# ssegs_and_registers.net
KiCad netlist of a schematic drawn in Altium Designer
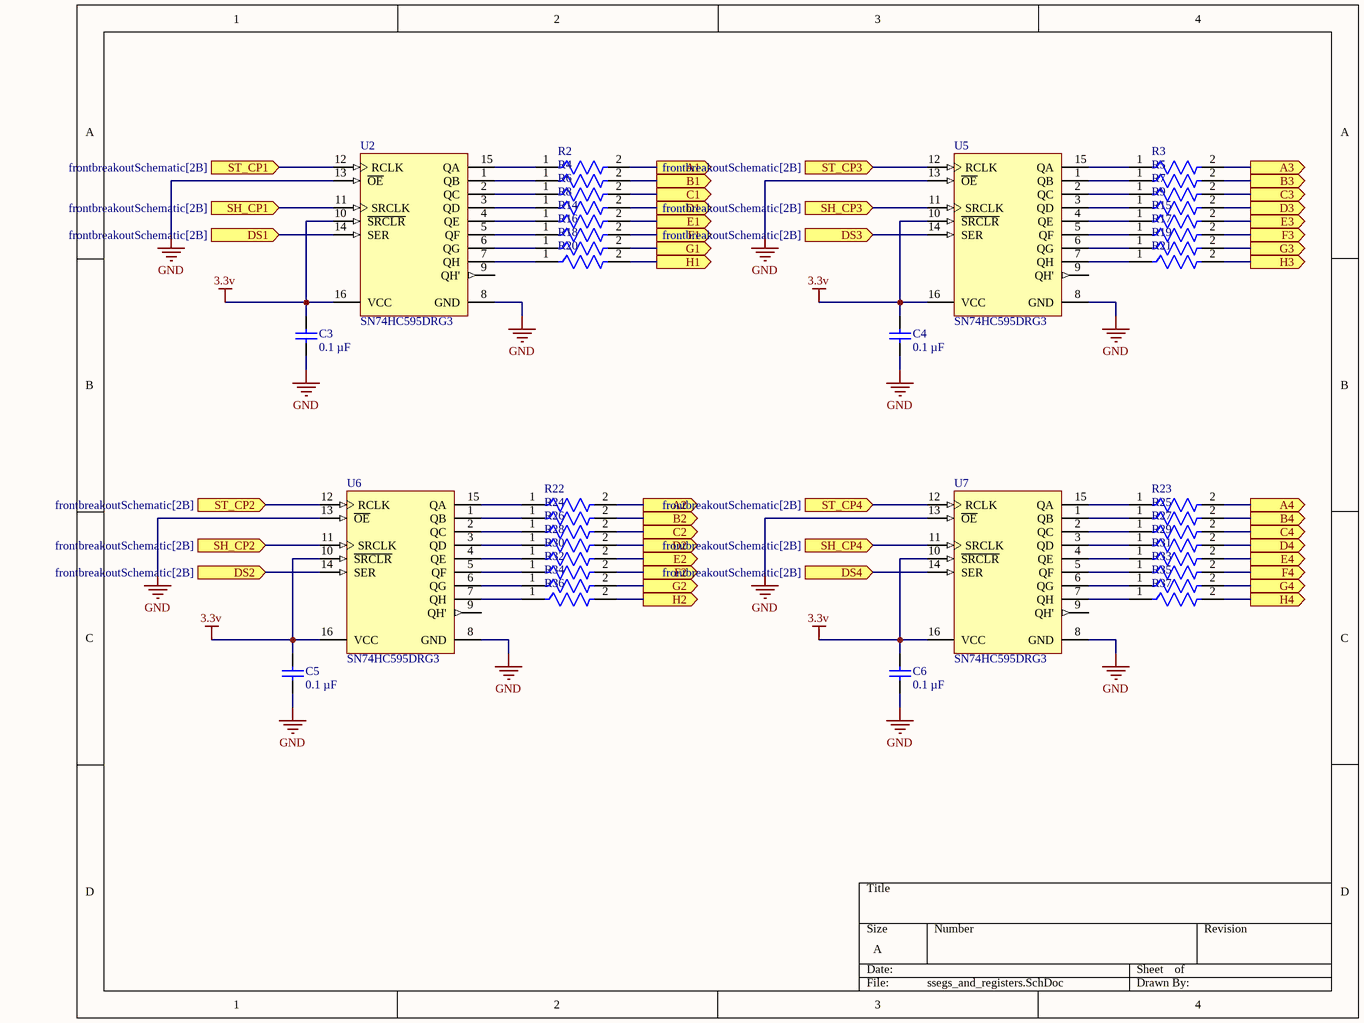
[diagram p0: ssegs_and_registers.SchDoc]

(export (version "E")
  (design (tool "Eeschema 10.0.6"))
  (components
    (comp (ref "C3")
      (value "0.1 µF")
      (footprint "CAPC2013X140X50NL20T25")
      (fields
        (field (name "PART NUMBER") "08055C104K4Z2A")
        (field (name "MANUFACTURER") "AVX Interconnect / Elco")
      )
      (libsource (lib "Altium Content Vault") (part "CAP"))
    )
    (comp (ref "C4")
      (value "0.1 µF")
      (footprint "CAPC2013X140X50NL20T25")
      (fields
        (field (name "PART NUMBER") "08055C104K4Z2A")
        (field (name "MANUFACTURER") "AVX Interconnect / Elco")
      )
      (libsource (lib "Altium Content Vault") (part "CAP"))
    )
    (comp (ref "C5")
      (value "0.1 µF")
      (footprint "CAPC2013X140X50NL20T25")
      (fields
        (field (name "PART NUMBER") "08055C104K4Z2A")
        (field (name "MANUFACTURER") "AVX Interconnect / Elco")
      )
      (libsource (lib "Altium Content Vault") (part "CAP"))
    )
    (comp (ref "C6")
      (value "0.1 µF")
      (footprint "CAPC2013X140X50NL20T25")
      (fields
        (field (name "PART NUMBER") "08055C104K4Z2A")
        (field (name "MANUFACTURER") "AVX Interconnect / Elco")
      )
      (libsource (lib "Altium Content Vault") (part "CAP"))
    )
    (comp (ref "R2")
      (value "200")
      (footprint "FP-RG2012-IPC_A")
      (description "Automotive Metal Thin Film Chip Resistor, 0805, 200Ω, 0.1%, 25ppm/°C, 0.125W, 150VRG2012P-201-B-T5")
      (fields (field (name "TOLERANCE") "0.1%"))
      (libsource (lib "Altium Content Vault") (part "1029c3af85768c4190bb7ad29bc67b5"))
    )
    (comp (ref "R3")
      (value "200")
      (footprint "FP-RG2012-IPC_A")
      (description "Automotive Metal Thin Film Chip Resistor, 0805, 200Ω, 0.1%, 25ppm/°C, 0.125W, 150VRG2012P-201-B-T5")
      (fields (field (name "TOLERANCE") "0.1%"))
      (libsource (lib "Altium Content Vault") (part "1029c3af85768c4190bb7ad29bc67b5"))
    )
    (comp (ref "R4")
      (value "200")
      (footprint "FP-RG2012-IPC_A")
      (description "Automotive Metal Thin Film Chip Resistor, 0805, 200Ω, 0.1%, 25ppm/°C, 0.125W, 150VRG2012P-201-B-T5")
      (fields (field (name "TOLERANCE") "0.1%"))
      (libsource (lib "Altium Content Vault") (part "1029c3af85768c4190bb7ad29bc67b5"))
    )
    (comp (ref "R5")
      (value "200")
      (footprint "FP-RG2012-IPC_A")
      (description "Automotive Metal Thin Film Chip Resistor, 0805, 200Ω, 0.1%, 25ppm/°C, 0.125W, 150VRG2012P-201-B-T5")
      (fields (field (name "TOLERANCE") "0.1%"))
      (libsource (lib "Altium Content Vault") (part "1029c3af85768c4190bb7ad29bc67b5"))
    )
    (comp (ref "R6")
      (value "200")
      (footprint "FP-RG2012-IPC_A")
      (description "Automotive Metal Thin Film Chip Resistor, 0805, 200Ω, 0.1%, 25ppm/°C, 0.125W, 150VRG2012P-201-B-T5")
      (fields (field (name "TOLERANCE") "0.1%"))
      (libsource (lib "Altium Content Vault") (part "1029c3af85768c4190bb7ad29bc67b5"))
    )
    (comp (ref "R7")
      (value "200")
      (footprint "FP-RG2012-IPC_A")
      (description "Automotive Metal Thin Film Chip Resistor, 0805, 200Ω, 0.1%, 25ppm/°C, 0.125W, 150VRG2012P-201-B-T5")
      (fields (field (name "TOLERANCE") "0.1%"))
      (libsource (lib "Altium Content Vault") (part "1029c3af85768c4190bb7ad29bc67b5"))
    )
    (comp (ref "R8")
      (value "200")
      (footprint "FP-RG2012-IPC_A")
      (description "Automotive Metal Thin Film Chip Resistor, 0805, 200Ω, 0.1%, 25ppm/°C, 0.125W, 150VRG2012P-201-B-T5")
      (fields (field (name "TOLERANCE") "0.1%"))
      (libsource (lib "Altium Content Vault") (part "1029c3af85768c4190bb7ad29bc67b5"))
    )
    (comp (ref "R9")
      (value "200")
      (footprint "FP-RG2012-IPC_A")
      (description "Automotive Metal Thin Film Chip Resistor, 0805, 200Ω, 0.1%, 25ppm/°C, 0.125W, 150VRG2012P-201-B-T5")
      (fields (field (name "TOLERANCE") "0.1%"))
      (libsource (lib "Altium Content Vault") (part "1029c3af85768c4190bb7ad29bc67b5"))
    )
    (comp (ref "R14")
      (value "200")
      (footprint "FP-RG2012-IPC_A")
      (description "Automotive Metal Thin Film Chip Resistor, 0805, 200Ω, 0.1%, 25ppm/°C, 0.125W, 150VRG2012P-201-B-T5")
      (fields (field (name "TOLERANCE") "0.1%"))
      (libsource (lib "Altium Content Vault") (part "1029c3af85768c4190bb7ad29bc67b5"))
    )
    (comp (ref "R15")
      (value "200")
      (footprint "FP-RG2012-IPC_A")
      (description "Automotive Metal Thin Film Chip Resistor, 0805, 200Ω, 0.1%, 25ppm/°C, 0.125W, 150VRG2012P-201-B-T5")
      (fields (field (name "TOLERANCE") "0.1%"))
      (libsource (lib "Altium Content Vault") (part "1029c3af85768c4190bb7ad29bc67b5"))
    )
    (comp (ref "R16")
      (value "200")
      (footprint "FP-RG2012-IPC_A")
      (description "Automotive Metal Thin Film Chip Resistor, 0805, 200Ω, 0.1%, 25ppm/°C, 0.125W, 150VRG2012P-201-B-T5")
      (fields (field (name "TOLERANCE") "0.1%"))
      (libsource (lib "Altium Content Vault") (part "1029c3af85768c4190bb7ad29bc67b5"))
    )
    (comp (ref "R17")
      (value "200")
      (footprint "FP-RG2012-IPC_A")
      (description "Automotive Metal Thin Film Chip Resistor, 0805, 200Ω, 0.1%, 25ppm/°C, 0.125W, 150VRG2012P-201-B-T5")
      (fields (field (name "TOLERANCE") "0.1%"))
      (libsource (lib "Altium Content Vault") (part "1029c3af85768c4190bb7ad29bc67b5"))
    )
    (comp (ref "R18")
      (value "200")
      (footprint "FP-RG2012-IPC_A")
      (description "Automotive Metal Thin Film Chip Resistor, 0805, 200Ω, 0.1%, 25ppm/°C, 0.125W, 150VRG2012P-201-B-T5")
      (fields (field (name "TOLERANCE") "0.1%"))
      (libsource (lib "Altium Content Vault") (part "1029c3af85768c4190bb7ad29bc67b5"))
    )
    (comp (ref "R19")
      (value "200")
      (footprint "FP-RG2012-IPC_A")
      (description "Automotive Metal Thin Film Chip Resistor, 0805, 200Ω, 0.1%, 25ppm/°C, 0.125W, 150VRG2012P-201-B-T5")
      (fields (field (name "TOLERANCE") "0.1%"))
      (libsource (lib "Altium Content Vault") (part "1029c3af85768c4190bb7ad29bc67b5"))
    )
    (comp (ref "R20")
      (value "200")
      (footprint "FP-RG2012-IPC_A")
      (description "Automotive Metal Thin Film Chip Resistor, 0805, 200Ω, 0.1%, 25ppm/°C, 0.125W, 150VRG2012P-201-B-T5")
      (fields (field (name "TOLERANCE") "0.1%"))
      (libsource (lib "Altium Content Vault") (part "1029c3af85768c4190bb7ad29bc67b5"))
    )
    (comp (ref "R21")
      (value "200")
      (footprint "FP-RG2012-IPC_A")
      (description "Automotive Metal Thin Film Chip Resistor, 0805, 200Ω, 0.1%, 25ppm/°C, 0.125W, 150VRG2012P-201-B-T5")
      (fields (field (name "TOLERANCE") "0.1%"))
      (libsource (lib "Altium Content Vault") (part "1029c3af85768c4190bb7ad29bc67b5"))
    )
    (comp (ref "R22")
      (value "200")
      (footprint "FP-RG2012-IPC_A")
      (description "Automotive Metal Thin Film Chip Resistor, 0805, 200Ω, 0.1%, 25ppm/°C, 0.125W, 150VRG2012P-201-B-T5")
      (fields (field (name "TOLERANCE") "0.1%"))
      (libsource (lib "Altium Content Vault") (part "1029c3af85768c4190bb7ad29bc67b5"))
    )
    (comp (ref "R23")
      (value "200")
      (footprint "FP-RG2012-IPC_A")
      (description "Automotive Metal Thin Film Chip Resistor, 0805, 200Ω, 0.1%, 25ppm/°C, 0.125W, 150VRG2012P-201-B-T5")
      (fields (field (name "TOLERANCE") "0.1%"))
      (libsource (lib "Altium Content Vault") (part "1029c3af85768c4190bb7ad29bc67b5"))
    )
    (comp (ref "R24")
      (value "200")
      (footprint "FP-RG2012-IPC_A")
      (description "Automotive Metal Thin Film Chip Resistor, 0805, 200Ω, 0.1%, 25ppm/°C, 0.125W, 150VRG2012P-201-B-T5")
      (fields (field (name "TOLERANCE") "0.1%"))
      (libsource (lib "Altium Content Vault") (part "1029c3af85768c4190bb7ad29bc67b5"))
    )
    (comp (ref "R25")
      (value "200")
      (footprint "FP-RG2012-IPC_A")
      (description "Automotive Metal Thin Film Chip Resistor, 0805, 200Ω, 0.1%, 25ppm/°C, 0.125W, 150VRG2012P-201-B-T5")
      (fields (field (name "TOLERANCE") "0.1%"))
      (libsource (lib "Altium Content Vault") (part "1029c3af85768c4190bb7ad29bc67b5"))
    )
    (comp (ref "R26")
      (value "200")
      (footprint "FP-RG2012-IPC_A")
      (description "Automotive Metal Thin Film Chip Resistor, 0805, 200Ω, 0.1%, 25ppm/°C, 0.125W, 150VRG2012P-201-B-T5")
      (fields (field (name "TOLERANCE") "0.1%"))
      (libsource (lib "Altium Content Vault") (part "1029c3af85768c4190bb7ad29bc67b5"))
    )
    (comp (ref "R27")
      (value "200")
      (footprint "FP-RG2012-IPC_A")
      (description "Automotive Metal Thin Film Chip Resistor, 0805, 200Ω, 0.1%, 25ppm/°C, 0.125W, 150VRG2012P-201-B-T5")
      (fields (field (name "TOLERANCE") "0.1%"))
      (libsource (lib "Altium Content Vault") (part "1029c3af85768c4190bb7ad29bc67b5"))
    )
    (comp (ref "R28")
      (value "200")
      (footprint "FP-RG2012-IPC_A")
      (description "Automotive Metal Thin Film Chip Resistor, 0805, 200Ω, 0.1%, 25ppm/°C, 0.125W, 150VRG2012P-201-B-T5")
      (fields (field (name "TOLERANCE") "0.1%"))
      (libsource (lib "Altium Content Vault") (part "1029c3af85768c4190bb7ad29bc67b5"))
    )
    (comp (ref "R29")
      (value "200")
      (footprint "FP-RG2012-IPC_A")
      (description "Automotive Metal Thin Film Chip Resistor, 0805, 200Ω, 0.1%, 25ppm/°C, 0.125W, 150VRG2012P-201-B-T5")
      (fields (field (name "TOLERANCE") "0.1%"))
      (libsource (lib "Altium Content Vault") (part "1029c3af85768c4190bb7ad29bc67b5"))
    )
    (comp (ref "R30")
      (value "200")
      (footprint "FP-RG2012-IPC_A")
      (description "Automotive Metal Thin Film Chip Resistor, 0805, 200Ω, 0.1%, 25ppm/°C, 0.125W, 150VRG2012P-201-B-T5")
      (fields (field (name "TOLERANCE") "0.1%"))
      (libsource (lib "Altium Content Vault") (part "1029c3af85768c4190bb7ad29bc67b5"))
    )
    (comp (ref "R31")
      (value "200")
      (footprint "FP-RG2012-IPC_A")
      (description "Automotive Metal Thin Film Chip Resistor, 0805, 200Ω, 0.1%, 25ppm/°C, 0.125W, 150VRG2012P-201-B-T5")
      (fields (field (name "TOLERANCE") "0.1%"))
      (libsource (lib "Altium Content Vault") (part "1029c3af85768c4190bb7ad29bc67b5"))
    )
    (comp (ref "R32")
      (value "200")
      (footprint "FP-RG2012-IPC_A")
      (description "Automotive Metal Thin Film Chip Resistor, 0805, 200Ω, 0.1%, 25ppm/°C, 0.125W, 150VRG2012P-201-B-T5")
      (fields (field (name "TOLERANCE") "0.1%"))
      (libsource (lib "Altium Content Vault") (part "1029c3af85768c4190bb7ad29bc67b5"))
    )
    (comp (ref "R33")
      (value "200")
      (footprint "FP-RG2012-IPC_A")
      (description "Automotive Metal Thin Film Chip Resistor, 0805, 200Ω, 0.1%, 25ppm/°C, 0.125W, 150VRG2012P-201-B-T5")
      (fields (field (name "TOLERANCE") "0.1%"))
      (libsource (lib "Altium Content Vault") (part "1029c3af85768c4190bb7ad29bc67b5"))
    )
    (comp (ref "R34")
      (value "200")
      (footprint "FP-RG2012-IPC_A")
      (description "Automotive Metal Thin Film Chip Resistor, 0805, 200Ω, 0.1%, 25ppm/°C, 0.125W, 150VRG2012P-201-B-T5")
      (fields (field (name "TOLERANCE") "0.1%"))
      (libsource (lib "Altium Content Vault") (part "1029c3af85768c4190bb7ad29bc67b5"))
    )
    (comp (ref "R35")
      (value "200")
      (footprint "FP-RG2012-IPC_A")
      (description "Automotive Metal Thin Film Chip Resistor, 0805, 200Ω, 0.1%, 25ppm/°C, 0.125W, 150VRG2012P-201-B-T5")
      (fields (field (name "TOLERANCE") "0.1%"))
      (libsource (lib "Altium Content Vault") (part "1029c3af85768c4190bb7ad29bc67b5"))
    )
    (comp (ref "R36")
      (value "200")
      (footprint "FP-RG2012-IPC_A")
      (description "Automotive Metal Thin Film Chip Resistor, 0805, 200Ω, 0.1%, 25ppm/°C, 0.125W, 150VRG2012P-201-B-T5")
      (fields (field (name "TOLERANCE") "0.1%"))
      (libsource (lib "Altium Content Vault") (part "1029c3af85768c4190bb7ad29bc67b5"))
    )
    (comp (ref "R37")
      (value "200")
      (footprint "FP-RG2012-IPC_A")
      (description "Automotive Metal Thin Film Chip Resistor, 0805, 200Ω, 0.1%, 25ppm/°C, 0.125W, 150VRG2012P-201-B-T5")
      (fields (field (name "TOLERANCE") "0.1%"))
      (libsource (lib "Altium Content Vault") (part "1029c3af85768c4190bb7ad29bc67b5"))
    )
    (comp (ref "U2")
      (value "SN74HC595DRG3")
      (footprint "D0016A_L")
      (description "8-Bit Shift Registers With 3-State Output Registers, D0016A, LARGE T&R")
      (fields
        (field (name "MANUFACTURER") "Texas Instruments")
        (field (name "GENERIC PART NUMBER") "SN74HC595")
      )
      (libsource (lib "Altium Content Vault") (part "TI-SN74XHCT595X_SN74LV595A-16"))
    )
    (comp (ref "U5")
      (value "SN74HC595DRG3")
      (footprint "D0016A_L")
      (description "8-Bit Shift Registers With 3-State Output Registers, D0016A, LARGE T&R")
      (fields
        (field (name "MANUFACTURER") "Texas Instruments")
        (field (name "GENERIC PART NUMBER") "SN74HC595")
      )
      (libsource (lib "Altium Content Vault") (part "TI-SN74XHCT595X_SN74LV595A-16"))
    )
    (comp (ref "U6")
      (value "SN74HC595DRG3")
      (footprint "D0016A_L")
      (description "8-Bit Shift Registers With 3-State Output Registers, D0016A, LARGE T&R")
      (fields
        (field (name "MANUFACTURER") "Texas Instruments")
        (field (name "GENERIC PART NUMBER") "SN74HC595")
      )
      (libsource (lib "Altium Content Vault") (part "TI-SN74XHCT595X_SN74LV595A-16"))
    )
    (comp (ref "U7")
      (value "SN74HC595DRG3")
      (footprint "D0016A_L")
      (description "8-Bit Shift Registers With 3-State Output Registers, D0016A, LARGE T&R")
      (fields
        (field (name "MANUFACTURER") "Texas Instruments")
        (field (name "GENERIC PART NUMBER") "SN74HC595")
      )
      (libsource (lib "Altium Content Vault") (part "TI-SN74XHCT595X_SN74LV595A-16"))
    )
  )
  (nets
    (net (code "1") (name "/A1") (class "Default")
      (node (ref "R2") (pin "2") (pinfunction "2_2") (pintype "passive"))
    )
    (net (code "2") (name "/A2") (class "Default")
      (node (ref "R22") (pin "2") (pinfunction "2_2") (pintype "passive"))
    )
    (net (code "3") (name "/A3") (class "Default")
      (node (ref "R3") (pin "2") (pinfunction "2_2") (pintype "passive"))
    )
    (net (code "4") (name "/A4") (class "Default")
      (node (ref "R23") (pin "2") (pinfunction "2_2") (pintype "passive"))
    )
    (net (code "5") (name "/B1") (class "Default")
      (node (ref "R4") (pin "2") (pinfunction "2_2") (pintype "passive"))
    )
    (net (code "6") (name "/B2") (class "Default")
      (node (ref "R24") (pin "2") (pinfunction "2_2") (pintype "passive"))
    )
    (net (code "7") (name "/B3") (class "Default")
      (node (ref "R5") (pin "2") (pinfunction "2_2") (pintype "passive"))
    )
    (net (code "8") (name "/B4") (class "Default")
      (node (ref "R25") (pin "2") (pinfunction "2_2") (pintype "passive"))
    )
    (net (code "9") (name "/C1") (class "Default")
      (node (ref "R6") (pin "2") (pinfunction "2_2") (pintype "passive"))
    )
    (net (code "10") (name "/C2") (class "Default")
      (node (ref "R26") (pin "2") (pinfunction "2_2") (pintype "passive"))
    )
    (net (code "11") (name "/C3") (class "Default")
      (node (ref "R7") (pin "2") (pinfunction "2_2") (pintype "passive"))
    )
    (net (code "12") (name "/C4") (class "Default")
      (node (ref "R27") (pin "2") (pinfunction "2_2") (pintype "passive"))
    )
    (net (code "13") (name "/D1") (class "Default")
      (node (ref "R8") (pin "2") (pinfunction "2_2") (pintype "passive"))
    )
    (net (code "14") (name "/D2") (class "Default")
      (node (ref "R28") (pin "2") (pinfunction "2_2") (pintype "passive"))
    )
    (net (code "15") (name "/D3") (class "Default")
      (node (ref "R9") (pin "2") (pinfunction "2_2") (pintype "passive"))
    )
    (net (code "16") (name "/D4") (class "Default")
      (node (ref "R29") (pin "2") (pinfunction "2_2") (pintype "passive"))
    )
    (net (code "17") (name "/DS1") (class "Default")
      (node (ref "U2") (pin "14") (pinfunction "SER_14") (pintype "input"))
    )
    (net (code "18") (name "/DS2") (class "Default")
      (node (ref "U6") (pin "14") (pinfunction "SER_14") (pintype "input"))
    )
    (net (code "19") (name "/DS3") (class "Default")
      (node (ref "U5") (pin "14") (pinfunction "SER_14") (pintype "input"))
    )
    (net (code "20") (name "/DS4") (class "Default")
      (node (ref "U7") (pin "14") (pinfunction "SER_14") (pintype "input"))
    )
    (net (code "21") (name "/E1") (class "Default")
      (node (ref "R14") (pin "2") (pinfunction "2_2") (pintype "passive"))
    )
    (net (code "22") (name "/E2") (class "Default")
      (node (ref "R30") (pin "2") (pinfunction "2_2") (pintype "passive"))
    )
    (net (code "23") (name "/E3") (class "Default")
      (node (ref "R15") (pin "2") (pinfunction "2_2") (pintype "passive"))
    )
    (net (code "24") (name "/E4") (class "Default")
      (node (ref "R31") (pin "2") (pinfunction "2_2") (pintype "passive"))
    )
    (net (code "25") (name "/F1") (class "Default")
      (node (ref "R16") (pin "2") (pinfunction "2_2") (pintype "passive"))
    )
    (net (code "26") (name "/F2") (class "Default")
      (node (ref "R32") (pin "2") (pinfunction "2_2") (pintype "passive"))
    )
    (net (code "27") (name "/F3") (class "Default")
      (node (ref "R17") (pin "2") (pinfunction "2_2") (pintype "passive"))
    )
    (net (code "28") (name "/F4") (class "Default")
      (node (ref "R33") (pin "2") (pinfunction "2_2") (pintype "passive"))
    )
    (net (code "29") (name "/G1") (class "Default")
      (node (ref "R18") (pin "2") (pinfunction "2_2") (pintype "passive"))
    )
    (net (code "30") (name "/G2") (class "Default")
      (node (ref "R34") (pin "2") (pinfunction "2_2") (pintype "passive"))
    )
    (net (code "31") (name "/G3") (class "Default")
      (node (ref "R19") (pin "2") (pinfunction "2_2") (pintype "passive"))
    )
    (net (code "32") (name "/G4") (class "Default")
      (node (ref "R35") (pin "2") (pinfunction "2_2") (pintype "passive"))
    )
    (net (code "33") (name "/H1") (class "Default")
      (node (ref "R20") (pin "2") (pinfunction "2_2") (pintype "passive"))
    )
    (net (code "34") (name "/H2") (class "Default")
      (node (ref "R36") (pin "2") (pinfunction "2_2") (pintype "passive"))
    )
    (net (code "35") (name "/H3") (class "Default")
      (node (ref "R21") (pin "2") (pinfunction "2_2") (pintype "passive"))
    )
    (net (code "36") (name "/H4") (class "Default")
      (node (ref "R37") (pin "2") (pinfunction "2_2") (pintype "passive"))
    )
    (net (code "37") (name "/SH_CP1") (class "Default")
      (node (ref "U2") (pin "11") (pinfunction "SRCLK_11") (pintype "input"))
    )
    (net (code "38") (name "/SH_CP2") (class "Default")
      (node (ref "U6") (pin "11") (pinfunction "SRCLK_11") (pintype "input"))
    )
    (net (code "39") (name "/SH_CP3") (class "Default")
      (node (ref "U5") (pin "11") (pinfunction "SRCLK_11") (pintype "input"))
    )
    (net (code "40") (name "/SH_CP4") (class "Default")
      (node (ref "U7") (pin "11") (pinfunction "SRCLK_11") (pintype "input"))
    )
    (net (code "41") (name "/ST_CP1") (class "Default")
      (node (ref "U2") (pin "12") (pinfunction "RCLK_12") (pintype "input"))
    )
    (net (code "42") (name "/ST_CP2") (class "Default")
      (node (ref "U6") (pin "12") (pinfunction "RCLK_12") (pintype "input"))
    )
    (net (code "43") (name "/ST_CP3") (class "Default")
      (node (ref "U5") (pin "12") (pinfunction "RCLK_12") (pintype "input"))
    )
    (net (code "44") (name "/ST_CP4") (class "Default")
      (node (ref "U7") (pin "12") (pinfunction "RCLK_12") (pintype "input"))
    )
    (net (code "45") (name "3.3v") (class "Default")
      (node (ref "C3") (pin "1") (pinfunction "1_1") (pintype "passive"))
      (node (ref "C4") (pin "1") (pinfunction "1_1") (pintype "passive"))
      (node (ref "C5") (pin "1") (pinfunction "1_1") (pintype "passive"))
      (node (ref "C6") (pin "1") (pinfunction "1_1") (pintype "passive"))
      (node (ref "U2") (pin "10") (pinfunction "~{SRCLR}_10") (pintype "input"))
      (node (ref "U2") (pin "16") (pinfunction "VCC_16") (pintype "power_in"))
      (node (ref "U5") (pin "10") (pinfunction "~{SRCLR}_10") (pintype "input"))
      (node (ref "U5") (pin "16") (pinfunction "VCC_16") (pintype "power_in"))
      (node (ref "U6") (pin "10") (pinfunction "~{SRCLR}_10") (pintype "input"))
      (node (ref "U6") (pin "16") (pinfunction "VCC_16") (pintype "power_in"))
      (node (ref "U7") (pin "10") (pinfunction "~{SRCLR}_10") (pintype "input"))
      (node (ref "U7") (pin "16") (pinfunction "VCC_16") (pintype "power_in"))
    )
    (net (code "46") (name "GND") (class "Default")
      (node (ref "C3") (pin "2") (pinfunction "2_2") (pintype "passive"))
      (node (ref "C4") (pin "2") (pinfunction "2_2") (pintype "passive"))
      (node (ref "C5") (pin "2") (pinfunction "2_2") (pintype "passive"))
      (node (ref "C6") (pin "2") (pinfunction "2_2") (pintype "passive"))
      (node (ref "U2") (pin "13") (pinfunction "~{OE}_13") (pintype "input"))
      (node (ref "U2") (pin "8") (pinfunction "GND_8") (pintype "power_in"))
      (node (ref "U5") (pin "13") (pinfunction "~{OE}_13") (pintype "input"))
      (node (ref "U5") (pin "8") (pinfunction "GND_8") (pintype "power_in"))
      (node (ref "U6") (pin "13") (pinfunction "~{OE}_13") (pintype "input"))
      (node (ref "U6") (pin "8") (pinfunction "GND_8") (pintype "power_in"))
      (node (ref "U7") (pin "13") (pinfunction "~{OE}_13") (pintype "input"))
      (node (ref "U7") (pin "8") (pinfunction "GND_8") (pintype "power_in"))
    )
    (net (code "47") (name "Net-(U2-QA)") (class "Default")
      (node (ref "R2") (pin "1") (pinfunction "1_1") (pintype "passive"))
      (node (ref "U2") (pin "15") (pinfunction "QA_15") (pintype "tri_state"))
    )
    (net (code "48") (name "Net-(U2-QB)") (class "Default")
      (node (ref "R4") (pin "1") (pinfunction "1_1") (pintype "passive"))
      (node (ref "U2") (pin "1") (pinfunction "QB_1") (pintype "tri_state"))
    )
    (net (code "49") (name "Net-(U2-QC)") (class "Default")
      (node (ref "R6") (pin "1") (pinfunction "1_1") (pintype "passive"))
      (node (ref "U2") (pin "2") (pinfunction "QC_2") (pintype "tri_state"))
    )
    (net (code "50") (name "Net-(U2-QD)") (class "Default")
      (node (ref "R8") (pin "1") (pinfunction "1_1") (pintype "passive"))
      (node (ref "U2") (pin "3") (pinfunction "QD_3") (pintype "tri_state"))
    )
    (net (code "51") (name "Net-(U2-QE)") (class "Default")
      (node (ref "R14") (pin "1") (pinfunction "1_1") (pintype "passive"))
      (node (ref "U2") (pin "4") (pinfunction "QE_4") (pintype "tri_state"))
    )
    (net (code "52") (name "Net-(U2-QF)") (class "Default")
      (node (ref "R16") (pin "1") (pinfunction "1_1") (pintype "passive"))
      (node (ref "U2") (pin "5") (pinfunction "QF_5") (pintype "tri_state"))
    )
    (net (code "53") (name "Net-(U2-QG)") (class "Default")
      (node (ref "R18") (pin "1") (pinfunction "1_1") (pintype "passive"))
      (node (ref "U2") (pin "6") (pinfunction "QG_6") (pintype "tri_state"))
    )
    (net (code "54") (name "Net-(U2-QH)") (class "Default")
      (node (ref "R20") (pin "1") (pinfunction "1_1") (pintype "passive"))
      (node (ref "U2") (pin "7") (pinfunction "QH_7") (pintype "tri_state"))
    )
    (net (code "55") (name "Net-(U5-QA)") (class "Default")
      (node (ref "R3") (pin "1") (pinfunction "1_1") (pintype "passive"))
      (node (ref "U5") (pin "15") (pinfunction "QA_15") (pintype "tri_state"))
    )
    (net (code "56") (name "Net-(U5-QB)") (class "Default")
      (node (ref "R5") (pin "1") (pinfunction "1_1") (pintype "passive"))
      (node (ref "U5") (pin "1") (pinfunction "QB_1") (pintype "tri_state"))
    )
    (net (code "57") (name "Net-(U5-QC)") (class "Default")
      (node (ref "R7") (pin "1") (pinfunction "1_1") (pintype "passive"))
      (node (ref "U5") (pin "2") (pinfunction "QC_2") (pintype "tri_state"))
    )
    (net (code "58") (name "Net-(U5-QD)") (class "Default")
      (node (ref "R9") (pin "1") (pinfunction "1_1") (pintype "passive"))
      (node (ref "U5") (pin "3") (pinfunction "QD_3") (pintype "tri_state"))
    )
    (net (code "59") (name "Net-(U5-QE)") (class "Default")
      (node (ref "R15") (pin "1") (pinfunction "1_1") (pintype "passive"))
      (node (ref "U5") (pin "4") (pinfunction "QE_4") (pintype "tri_state"))
    )
    (net (code "60") (name "Net-(U5-QF)") (class "Default")
      (node (ref "R17") (pin "1") (pinfunction "1_1") (pintype "passive"))
      (node (ref "U5") (pin "5") (pinfunction "QF_5") (pintype "tri_state"))
    )
    (net (code "61") (name "Net-(U5-QG)") (class "Default")
      (node (ref "R19") (pin "1") (pinfunction "1_1") (pintype "passive"))
      (node (ref "U5") (pin "6") (pinfunction "QG_6") (pintype "tri_state"))
    )
    (net (code "62") (name "Net-(U5-QH)") (class "Default")
      (node (ref "R21") (pin "1") (pinfunction "1_1") (pintype "passive"))
      (node (ref "U5") (pin "7") (pinfunction "QH_7") (pintype "tri_state"))
    )
    (net (code "63") (name "Net-(U6-QA)") (class "Default")
      (node (ref "R22") (pin "1") (pinfunction "1_1") (pintype "passive"))
      (node (ref "U6") (pin "15") (pinfunction "QA_15") (pintype "tri_state"))
    )
    (net (code "64") (name "Net-(U6-QB)") (class "Default")
      (node (ref "R24") (pin "1") (pinfunction "1_1") (pintype "passive"))
      (node (ref "U6") (pin "1") (pinfunction "QB_1") (pintype "tri_state"))
    )
    (net (code "65") (name "Net-(U6-QC)") (class "Default")
      (node (ref "R26") (pin "1") (pinfunction "1_1") (pintype "passive"))
      (node (ref "U6") (pin "2") (pinfunction "QC_2") (pintype "tri_state"))
    )
    (net (code "66") (name "Net-(U6-QD)") (class "Default")
      (node (ref "R28") (pin "1") (pinfunction "1_1") (pintype "passive"))
      (node (ref "U6") (pin "3") (pinfunction "QD_3") (pintype "tri_state"))
    )
    (net (code "67") (name "Net-(U6-QE)") (class "Default")
      (node (ref "R30") (pin "1") (pinfunction "1_1") (pintype "passive"))
      (node (ref "U6") (pin "4") (pinfunction "QE_4") (pintype "tri_state"))
    )
    (net (code "68") (name "Net-(U6-QF)") (class "Default")
      (node (ref "R32") (pin "1") (pinfunction "1_1") (pintype "passive"))
      (node (ref "U6") (pin "5") (pinfunction "QF_5") (pintype "tri_state"))
    )
    (net (code "69") (name "Net-(U6-QG)") (class "Default")
      (node (ref "R34") (pin "1") (pinfunction "1_1") (pintype "passive"))
      (node (ref "U6") (pin "6") (pinfunction "QG_6") (pintype "tri_state"))
    )
    (net (code "70") (name "Net-(U6-QH)") (class "Default")
      (node (ref "R36") (pin "1") (pinfunction "1_1") (pintype "passive"))
      (node (ref "U6") (pin "7") (pinfunction "QH_7") (pintype "tri_state"))
    )
    (net (code "71") (name "Net-(U7-QA)") (class "Default")
      (node (ref "R23") (pin "1") (pinfunction "1_1") (pintype "passive"))
      (node (ref "U7") (pin "15") (pinfunction "QA_15") (pintype "tri_state"))
    )
    (net (code "72") (name "Net-(U7-QB)") (class "Default")
      (node (ref "R25") (pin "1") (pinfunction "1_1") (pintype "passive"))
      (node (ref "U7") (pin "1") (pinfunction "QB_1") (pintype "tri_state"))
    )
    (net (code "73") (name "Net-(U7-QC)") (class "Default")
      (node (ref "R27") (pin "1") (pinfunction "1_1") (pintype "passive"))
      (node (ref "U7") (pin "2") (pinfunction "QC_2") (pintype "tri_state"))
    )
    (net (code "74") (name "Net-(U7-QD)") (class "Default")
      (node (ref "R29") (pin "1") (pinfunction "1_1") (pintype "passive"))
      (node (ref "U7") (pin "3") (pinfunction "QD_3") (pintype "tri_state"))
    )
    (net (code "75") (name "Net-(U7-QE)") (class "Default")
      (node (ref "R31") (pin "1") (pinfunction "1_1") (pintype "passive"))
      (node (ref "U7") (pin "4") (pinfunction "QE_4") (pintype "tri_state"))
    )
    (net (code "76") (name "Net-(U7-QF)") (class "Default")
      (node (ref "R33") (pin "1") (pinfunction "1_1") (pintype "passive"))
      (node (ref "U7") (pin "5") (pinfunction "QF_5") (pintype "tri_state"))
    )
    (net (code "77") (name "Net-(U7-QG)") (class "Default")
      (node (ref "R35") (pin "1") (pinfunction "1_1") (pintype "passive"))
      (node (ref "U7") (pin "6") (pinfunction "QG_6") (pintype "tri_state"))
    )
    (net (code "78") (name "Net-(U7-QH)") (class "Default")
      (node (ref "R37") (pin "1") (pinfunction "1_1") (pintype "passive"))
      (node (ref "U7") (pin "7") (pinfunction "QH_7") (pintype "tri_state"))
    )
    (net (code "79") (name "unconnected-(U2-QH'-Pad9)") (class "Default")
      (node (ref "U2") (pin "9") (pinfunction "QH'_9") (pintype "output"))
    )
    (net (code "80") (name "unconnected-(U5-QH'-Pad9)") (class "Default")
      (node (ref "U5") (pin "9") (pinfunction "QH'_9") (pintype "output"))
    )
    (net (code "81") (name "unconnected-(U6-QH'-Pad9)") (class "Default")
      (node (ref "U6") (pin "9") (pinfunction "QH'_9") (pintype "output"))
    )
    (net (code "82") (name "unconnected-(U7-QH'-Pad9)") (class "Default")
      (node (ref "U7") (pin "9") (pinfunction "QH'_9") (pintype "output"))
    )
  )
)
